# stm32103c8t6-10x10-v1.net
KiCad netlist of a schematic drawn in EAGLE
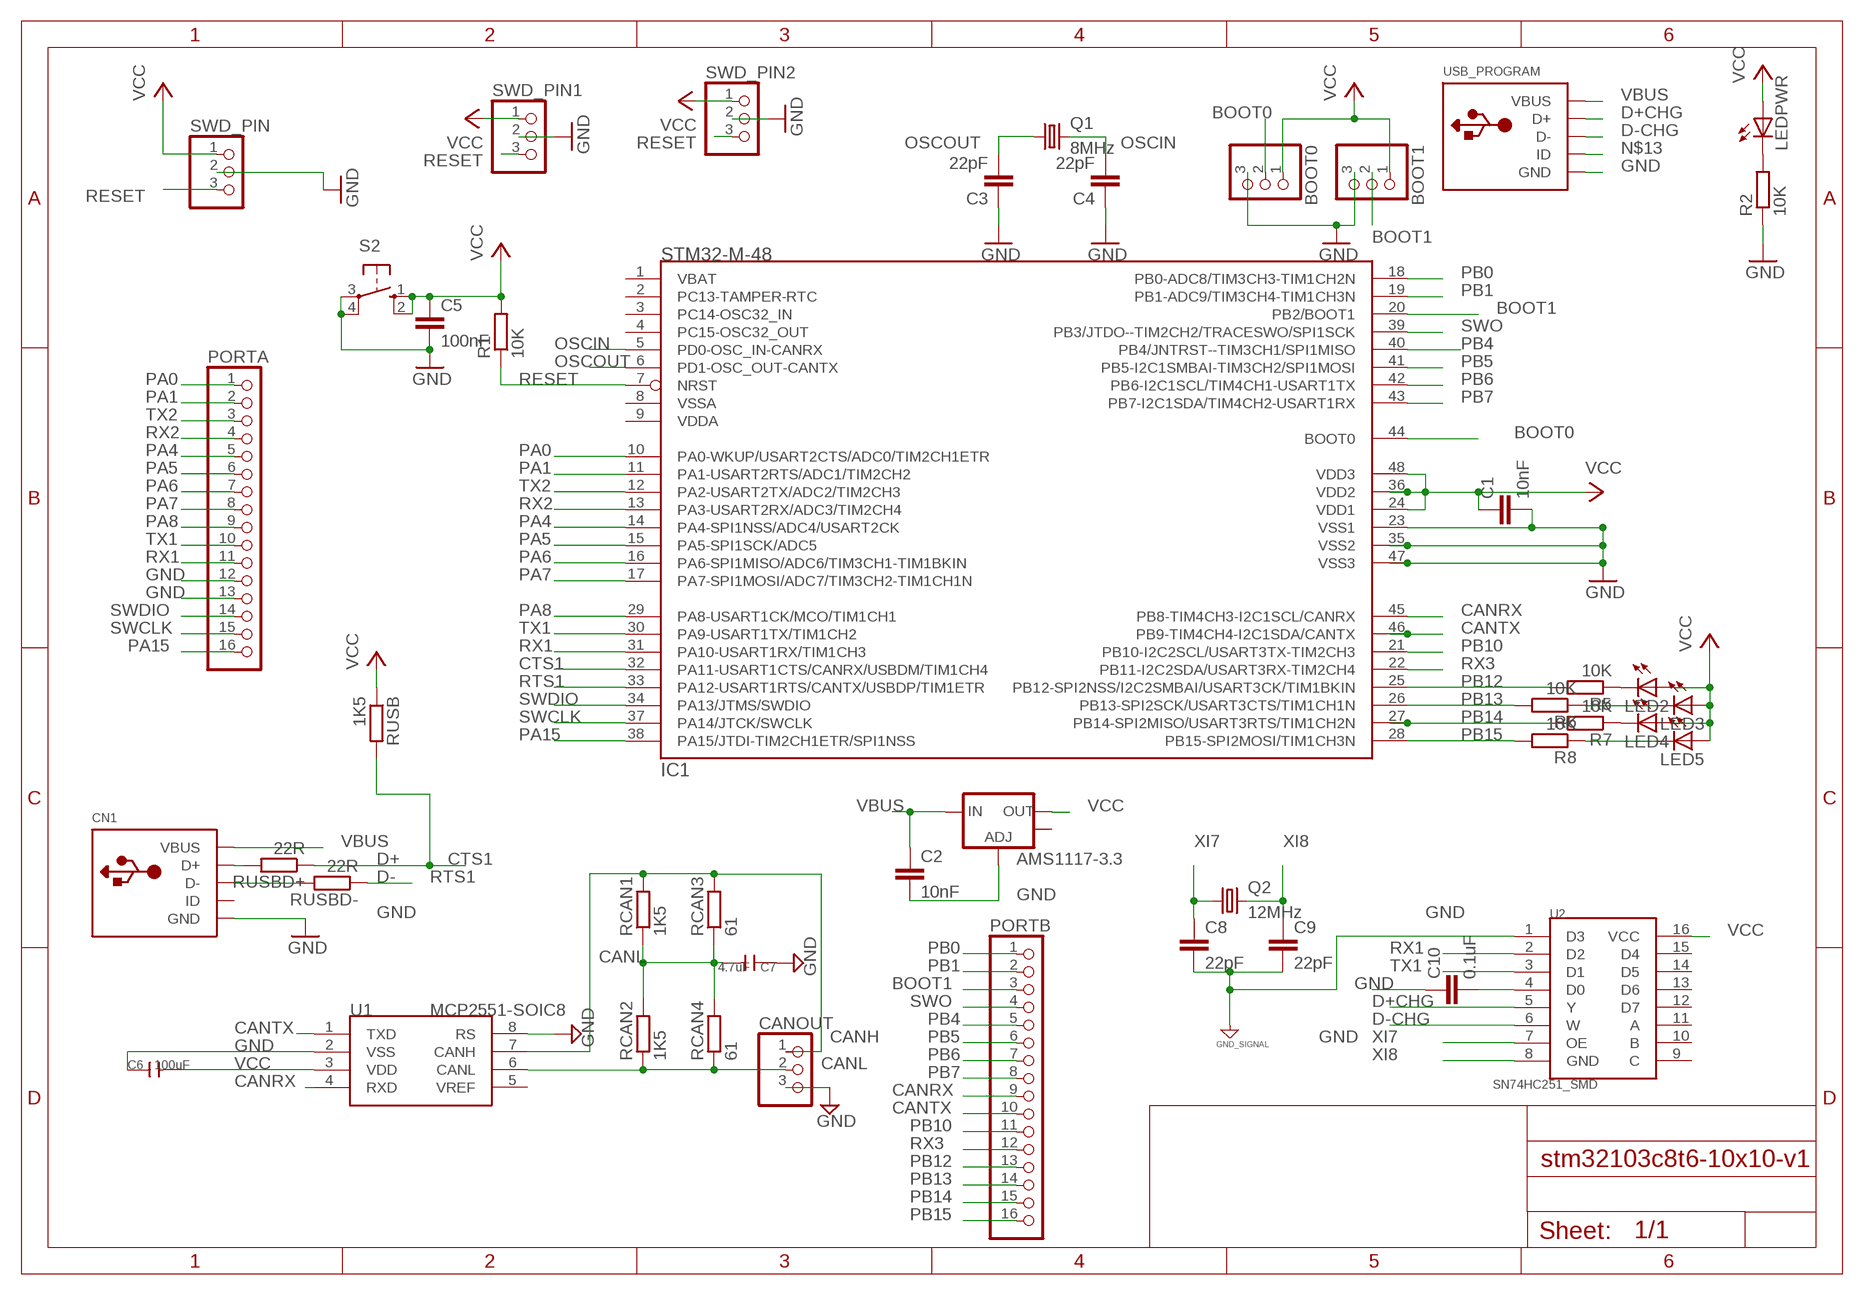
[diagram p0: schematic, sheet 1]

(export (version "E")
  (design (tool "Eeschema 10.0.6"))
  (components
    (comp (ref "AMS1117-3.3")
      (value "V_REG_LM1117SOT223")
      (footprint "eagle-import:SOT223")
      (libsource (lib "eagle-import") (part "V_REG_LM1117SOT223"))
    )
    (comp (ref "BOOT0")
      (value "PINHD-1X3")
      (footprint "eagle-import:1X03")
      (libsource (lib "eagle-import") (part "PINHD-1X3"))
    )
    (comp (ref "BOOT1")
      (value "PINHD-1X3")
      (footprint "eagle-import:1X03")
      (libsource (lib "eagle-import") (part "PINHD-1X3"))
    )
    (comp (ref "C1")
      (value "10nF")
      (footprint "eagle-import:C1210")
      (libsource (lib "eagle-import") (part "C-EUC1210"))
    )
    (comp (ref "C2")
      (value "10nF")
      (footprint "eagle-import:C1206")
      (libsource (lib "eagle-import") (part "C-EUC1206"))
    )
    (comp (ref "C3")
      (value "22pF")
      (footprint "eagle-import:C1210")
      (libsource (lib "eagle-import") (part "C-EUC1210"))
    )
    (comp (ref "C4")
      (value "22pF")
      (footprint "eagle-import:C1210")
      (libsource (lib "eagle-import") (part "C-EUC1210"))
    )
    (comp (ref "C5")
      (value "100nF")
      (footprint "eagle-import:C1206")
      (libsource (lib "eagle-import") (part "C-EUC1206"))
    )
    (comp (ref "C6")
      (value "100uF")
      (footprint "eagle-import:C1206")
      (libsource (lib "eagle-import") (part "C-1206"))
    )
    (comp (ref "C7")
      (value "4.7uF")
      (footprint "eagle-import:C1206")
      (libsource (lib "eagle-import") (part "C-1206"))
    )
    (comp (ref "C8")
      (value "22pF")
      (footprint "eagle-import:C1206")
      (libsource (lib "eagle-import") (part "C-EUC1206"))
    )
    (comp (ref "C9")
      (value "22pF")
      (footprint "eagle-import:C1206")
      (libsource (lib "eagle-import") (part "C-EUC1206"))
    )
    (comp (ref "C10")
      (value "0.1uF")
      (footprint "eagle-import:C1206")
      (libsource (lib "eagle-import") (part "C-EUC1206"))
    )
    (comp (ref "CANOUT")
      (value "PINHD-1X3")
      (footprint "eagle-import:1X03")
      (libsource (lib "eagle-import") (part "PINHD-1X3"))
    )
    (comp (ref "CN1")
      (value "USBTHM")
      (footprint "eagle-import:USB-MINIB-THM")
      (libsource (lib "eagle-import") (part "USBTHM"))
    )
    (comp (ref "IC1")
      (value "STM32-M-48")
      (footprint "eagle-import:LQFP48")
      (libsource (lib "eagle-import") (part "STM32-M-48"))
    )
    (comp (ref "LED2")
      (value "LEDSMT1206")
      (footprint "eagle-import:1206")
      (libsource (lib "eagle-import") (part "LEDSMT1206"))
    )
    (comp (ref "LED3")
      (value "LEDSMT1206")
      (footprint "eagle-import:1206")
      (libsource (lib "eagle-import") (part "LEDSMT1206"))
    )
    (comp (ref "LED4")
      (value "LEDSMT1206")
      (footprint "eagle-import:1206")
      (libsource (lib "eagle-import") (part "LEDSMT1206"))
    )
    (comp (ref "LED5")
      (value "LEDSMT1206")
      (footprint "eagle-import:1206")
      (libsource (lib "eagle-import") (part "LEDSMT1206"))
    )
    (comp (ref "LEDPWR")
      (value "LEDSMT1206")
      (footprint "eagle-import:1206")
      (libsource (lib "eagle-import") (part "LEDSMT1206"))
    )
    (comp (ref "PORTA")
      (value "PINHD-1X16")
      (footprint "eagle-import:1X16")
      (libsource (lib "eagle-import") (part "PINHD-1X16"))
    )
    (comp (ref "PORTB")
      (value "PINHD-1X16")
      (footprint "eagle-import:1X16")
      (libsource (lib "eagle-import") (part "PINHD-1X16"))
    )
    (comp (ref "Q1")
      (value "8MHz")
      (footprint "eagle-import:HC49_S")
      (libsource (lib "eagle-import") (part "CRYSTALHC49S"))
    )
    (comp (ref "Q2")
      (value "12MHz")
      (footprint "eagle-import:HC49_S")
      (libsource (lib "eagle-import") (part "CRYSTALHC49S"))
    )
    (comp (ref "R1")
      (value "10K")
      (footprint "eagle-import:R1206")
      (libsource (lib "eagle-import") (part "R-EU_R1206"))
    )
    (comp (ref "R2")
      (value "10K")
      (footprint "eagle-import:R1206")
      (libsource (lib "eagle-import") (part "R-EU_R1206"))
    )
    (comp (ref "R5")
      (value "10K")
      (footprint "eagle-import:R1206")
      (libsource (lib "eagle-import") (part "R-EU_R1206"))
    )
    (comp (ref "R6")
      (value "10K")
      (footprint "eagle-import:R1206")
      (libsource (lib "eagle-import") (part "R-EU_R1206"))
    )
    (comp (ref "R7")
      (value "10K")
      (footprint "eagle-import:R1206")
      (libsource (lib "eagle-import") (part "R-EU_R1206"))
    )
    (comp (ref "R8")
      (value "10K")
      (footprint "eagle-import:R1206")
      (libsource (lib "eagle-import") (part "R-EU_R1206"))
    )
    (comp (ref "RCAN1")
      (value "1K5")
      (footprint "eagle-import:R1206")
      (libsource (lib "eagle-import") (part "R-EU_R1206"))
    )
    (comp (ref "RCAN2")
      (value "1K5")
      (footprint "eagle-import:R1206")
      (libsource (lib "eagle-import") (part "R-EU_R1206"))
    )
    (comp (ref "RCAN3")
      (value "61")
      (footprint "eagle-import:R1206")
      (libsource (lib "eagle-import") (part "R-EU_R1206"))
    )
    (comp (ref "RCAN4")
      (value "61")
      (footprint "eagle-import:R1206")
      (libsource (lib "eagle-import") (part "R-EU_R1206"))
    )
    (comp (ref "RUSB")
      (value "1K5")
      (footprint "eagle-import:R1206")
      (libsource (lib "eagle-import") (part "R-EU_R1206"))
    )
    (comp (ref "RUSBD+")
      (value "22R")
      (footprint "eagle-import:R1206")
      (libsource (lib "eagle-import") (part "R-EU_R1206"))
    )
    (comp (ref "RUSBD-")
      (value "22R")
      (footprint "eagle-import:R1206")
      (libsource (lib "eagle-import") (part "R-EU_R1206"))
    )
    (comp (ref "S2")
      (value "10-XX")
      (footprint "eagle-import:B3F-10XX")
      (fields (field (name "MPN") "B3F-1000"))
      (libsource (lib "eagle-import") (part "10-XX"))
    )
    (comp (ref "SWD_PIN")
      (value "PINHD-1X3")
      (footprint "eagle-import:1X03")
      (libsource (lib "eagle-import") (part "PINHD-1X3"))
    )
    (comp (ref "SWD_PIN1")
      (value "PINHD-1X3")
      (footprint "eagle-import:1X03")
      (libsource (lib "eagle-import") (part "PINHD-1X3"))
    )
    (comp (ref "SWD_PIN2")
      (value "PINHD-1X3")
      (footprint "eagle-import:1X03")
      (libsource (lib "eagle-import") (part "PINHD-1X3"))
    )
    (comp (ref "U1")
      (value "MCP2551-SOIC8")
      (footprint "eagle-import:SOIC8-6.0")
      (libsource (lib "eagle-import") (part "MCP2551-SOIC8"))
    )
    (comp (ref "U2")
      (value "SN74HC251_SMD")
      (footprint "eagle-import:SO016")
      (libsource (lib "eagle-import") (part "SN74HC251_SMD"))
    )
    (comp (ref "USB_PROGRAM")
      (value "USBTHM")
      (footprint "eagle-import:USB-MINIB-THM")
      (libsource (lib "eagle-import") (part "USBTHM"))
    )
  )
  (nets
    (net (code "1") (name "/BOOT0") (class "Default")
      (node (ref "BOOT0") (pin "2") (pinfunction "2_2") (pintype "passive"))
      (node (ref "IC1") (pin "44") (pinfunction "BOOT0_44") (pintype "input"))
    )
    (net (code "2") (name "/BOOT1") (class "Default")
      (node (ref "BOOT1") (pin "2") (pinfunction "2_2") (pintype "passive"))
      (node (ref "IC1") (pin "20") (pinfunction "PB2/BOOT1_20") (pintype "bidirectional"))
      (node (ref "PORTB") (pin "3") (pinfunction "3_3") (pintype "passive"))
    )
    (net (code "3") (name "/CANH") (class "Default")
      (node (ref "CANOUT") (pin "1") (pinfunction "1_1") (pintype "passive"))
      (node (ref "RCAN1") (pin "2") (pinfunction "2_2") (pintype "passive"))
      (node (ref "RCAN3") (pin "2") (pinfunction "2_2") (pintype "passive"))
      (node (ref "U1") (pin "7") (pinfunction "CANH_7") (pintype "bidirectional"))
    )
    (net (code "4") (name "/CANL") (class "Default")
      (node (ref "CANOUT") (pin "2") (pinfunction "2_2") (pintype "passive"))
      (node (ref "RCAN2") (pin "1") (pinfunction "1_1") (pintype "passive"))
      (node (ref "RCAN4") (pin "1") (pinfunction "1_1") (pintype "passive"))
      (node (ref "U1") (pin "6") (pinfunction "CANL_6") (pintype "bidirectional"))
    )
    (net (code "5") (name "/CANRX") (class "Default")
      (node (ref "IC1") (pin "45") (pinfunction "PB8-TIM4CH3-I2C1SCL/CANRX_45") (pintype "bidirectional"))
      (node (ref "PORTB") (pin "9") (pinfunction "9_9") (pintype "passive"))
      (node (ref "U1") (pin "4") (pinfunction "RXD_4") (pintype "bidirectional"))
    )
    (net (code "6") (name "/CANTX") (class "Default")
      (node (ref "IC1") (pin "46") (pinfunction "PB9-TIM4CH4-I2C1SDA/CANTX_46") (pintype "bidirectional"))
      (node (ref "PORTB") (pin "10") (pinfunction "10_10") (pintype "passive"))
      (node (ref "U1") (pin "1") (pinfunction "TXD_1") (pintype "bidirectional"))
    )
    (net (code "7") (name "/CTS1") (class "Default")
      (node (ref "IC1") (pin "32") (pinfunction "PA11-USART1CTS/CANRX/USBDM/TIM1CH4_32") (pintype "bidirectional"))
      (node (ref "RUSB") (pin "2") (pinfunction "2_2") (pintype "passive"))
      (node (ref "RUSBD+") (pin "1") (pinfunction "1_1") (pintype "passive"))
    )
    (net (code "8") (name "/D+") (class "Default")
      (node (ref "CN1") (pin "D+") (pinfunction "D+_D+") (pintype "bidirectional"))
      (node (ref "RUSBD+") (pin "2") (pinfunction "2_2") (pintype "passive"))
    )
    (net (code "9") (name "/D+CHG") (class "Default")
      (node (ref "U2") (pin "5") (pinfunction "Y_5") (pintype "bidirectional"))
      (node (ref "USB_PROGRAM") (pin "D+") (pinfunction "D+_D+") (pintype "bidirectional"))
    )
    (net (code "10") (name "/D-") (class "Default")
      (node (ref "CN1") (pin "D-") (pinfunction "D-_D-") (pintype "bidirectional"))
      (node (ref "RUSBD-") (pin "2") (pinfunction "2_2") (pintype "passive"))
    )
    (net (code "11") (name "/D-CHG") (class "Default")
      (node (ref "U2") (pin "6") (pinfunction "W_6") (pintype "bidirectional"))
      (node (ref "USB_PROGRAM") (pin "D-") (pinfunction "D-_D-") (pintype "bidirectional"))
    )
    (net (code "12") (name "/N$13") (class "Default")
      (node (ref "USB_PROGRAM") (pin "ID") (pinfunction "ID_ID") (pintype "bidirectional"))
    )
    (net (code "13") (name "/OSCIN") (class "Default")
      (node (ref "C4") (pin "2") (pinfunction "2_2") (pintype "passive"))
      (node (ref "IC1") (pin "5") (pinfunction "PD0-OSC_IN-CANRX_5") (pintype "input"))
      (node (ref "Q1") (pin "2") (pinfunction "2_2") (pintype "passive"))
    )
    (net (code "14") (name "/OSCOUT") (class "Default")
      (node (ref "C3") (pin "2") (pinfunction "2_2") (pintype "passive"))
      (node (ref "IC1") (pin "6") (pinfunction "PD1-OSC_OUT-CANTX_6") (pintype "output"))
      (node (ref "Q1") (pin "1") (pinfunction "1_1") (pintype "passive"))
    )
    (net (code "15") (name "/PA0") (class "Default")
      (node (ref "IC1") (pin "10") (pinfunction "PA0-WKUP/USART2CTS/ADC0/TIM2CH1ETR_10") (pintype "bidirectional"))
      (node (ref "PORTA") (pin "1") (pinfunction "1_1") (pintype "passive"))
    )
    (net (code "16") (name "/PA1") (class "Default")
      (node (ref "IC1") (pin "11") (pinfunction "PA1-USART2RTS/ADC1/TIM2CH2_11") (pintype "bidirectional"))
      (node (ref "PORTA") (pin "2") (pinfunction "2_2") (pintype "passive"))
    )
    (net (code "17") (name "/PA4") (class "Default")
      (node (ref "IC1") (pin "14") (pinfunction "PA4-SPI1NSS/ADC4/USART2CK_14") (pintype "bidirectional"))
      (node (ref "PORTA") (pin "5") (pinfunction "5_5") (pintype "passive"))
    )
    (net (code "18") (name "/PA5") (class "Default")
      (node (ref "IC1") (pin "15") (pinfunction "PA5-SPI1SCK/ADC5_15") (pintype "bidirectional"))
      (node (ref "PORTA") (pin "6") (pinfunction "6_6") (pintype "passive"))
    )
    (net (code "19") (name "/PA6") (class "Default")
      (node (ref "IC1") (pin "16") (pinfunction "PA6-SPI1MISO/ADC6/TIM3CH1-TIM1BKIN_16") (pintype "bidirectional"))
      (node (ref "PORTA") (pin "7") (pinfunction "7_7") (pintype "passive"))
    )
    (net (code "20") (name "/PA7") (class "Default")
      (node (ref "IC1") (pin "17") (pinfunction "PA7-SPI1MOSI/ADC7/TIM3CH2-TIM1CH1N_17") (pintype "bidirectional"))
      (node (ref "PORTA") (pin "8") (pinfunction "8_8") (pintype "passive"))
    )
    (net (code "21") (name "/PA8") (class "Default")
      (node (ref "IC1") (pin "29") (pinfunction "PA8-USART1CK/MCO/TIM1CH1_29") (pintype "bidirectional"))
      (node (ref "PORTA") (pin "9") (pinfunction "9_9") (pintype "passive"))
    )
    (net (code "22") (name "/PA15") (class "Default")
      (node (ref "IC1") (pin "38") (pinfunction "PA15/JTDI-TIM2CH1ETR/SPI1NSS_38") (pintype "bidirectional"))
      (node (ref "PORTA") (pin "16") (pinfunction "16_16") (pintype "passive"))
    )
    (net (code "23") (name "/PB0") (class "Default")
      (node (ref "IC1") (pin "18") (pinfunction "PB0-ADC8/TIM3CH3-TIM1CH2N_18") (pintype "bidirectional"))
      (node (ref "PORTB") (pin "1") (pinfunction "1_1") (pintype "passive"))
    )
    (net (code "24") (name "/PB1") (class "Default")
      (node (ref "IC1") (pin "19") (pinfunction "PB1-ADC9/TIM3CH4-TIM1CH3N_19") (pintype "bidirectional"))
      (node (ref "PORTB") (pin "2") (pinfunction "2_2") (pintype "passive"))
    )
    (net (code "25") (name "/PB4") (class "Default")
      (node (ref "IC1") (pin "40") (pinfunction "PB4/JNTRST--TIM3CH1/SPI1MISO_40") (pintype "bidirectional"))
      (node (ref "PORTB") (pin "5") (pinfunction "5_5") (pintype "passive"))
    )
    (net (code "26") (name "/PB5") (class "Default")
      (node (ref "IC1") (pin "41") (pinfunction "PB5-I2C1SMBAI-TIM3CH2/SPI1MOSI_41") (pintype "bidirectional"))
      (node (ref "PORTB") (pin "6") (pinfunction "6_6") (pintype "passive"))
    )
    (net (code "27") (name "/PB6") (class "Default")
      (node (ref "IC1") (pin "42") (pinfunction "PB6-I2C1SCL/TIM4CH1-USART1TX_42") (pintype "bidirectional"))
      (node (ref "PORTB") (pin "7") (pinfunction "7_7") (pintype "passive"))
    )
    (net (code "28") (name "/PB7") (class "Default")
      (node (ref "IC1") (pin "43") (pinfunction "PB7-I2C1SDA/TIM4CH2-USART1RX_43") (pintype "bidirectional"))
      (node (ref "PORTB") (pin "8") (pinfunction "8_8") (pintype "passive"))
    )
    (net (code "29") (name "/PB10") (class "Default")
      (node (ref "IC1") (pin "21") (pinfunction "PB10-I2C2SCL/USART3TX-TIM2CH3_21") (pintype "bidirectional"))
      (node (ref "PORTB") (pin "11") (pinfunction "11_11") (pintype "passive"))
    )
    (net (code "30") (name "/PB12") (class "Default")
      (node (ref "IC1") (pin "25") (pinfunction "PB12-SPI2NSS/I2C2SMBAI/USART3CK/TIM1BKIN_25") (pintype "bidirectional"))
      (node (ref "PORTB") (pin "13") (pinfunction "13_13") (pintype "passive"))
      (node (ref "R5") (pin "2") (pinfunction "2_2") (pintype "passive"))
    )
    (net (code "31") (name "/PB13") (class "Default")
      (node (ref "IC1") (pin "26") (pinfunction "PB13-SPI2SCK/USART3CTS/TIM1CH1N_26") (pintype "bidirectional"))
      (node (ref "PORTB") (pin "14") (pinfunction "14_14") (pintype "passive"))
      (node (ref "R6") (pin "2") (pinfunction "2_2") (pintype "passive"))
    )
    (net (code "32") (name "/PB14") (class "Default")
      (node (ref "IC1") (pin "27") (pinfunction "PB14-SPI2MISO/USART3RTS/TIM1CH2N_27") (pintype "bidirectional"))
      (node (ref "PORTB") (pin "15") (pinfunction "15_15") (pintype "passive"))
      (node (ref "R7") (pin "2") (pinfunction "2_2") (pintype "passive"))
    )
    (net (code "33") (name "/PB15") (class "Default")
      (node (ref "IC1") (pin "28") (pinfunction "PB15-SPI2MOSI/TIM1CH3N_28") (pintype "bidirectional"))
      (node (ref "PORTB") (pin "16") (pinfunction "16_16") (pintype "passive"))
      (node (ref "R8") (pin "2") (pinfunction "2_2") (pintype "passive"))
    )
    (net (code "34") (name "/RESET") (class "Default")
      (node (ref "IC1") (pin "7") (pinfunction "NRST_7") (pintype "bidirectional"))
      (node (ref "R1") (pin "1") (pinfunction "1_1") (pintype "passive"))
      (node (ref "SWD_PIN") (pin "3") (pinfunction "3_3") (pintype "passive"))
      (node (ref "SWD_PIN1") (pin "3") (pinfunction "3_3") (pintype "passive"))
      (node (ref "SWD_PIN2") (pin "3") (pinfunction "3_3") (pintype "passive"))
    )
    (net (code "35") (name "/RTS1") (class "Default")
      (node (ref "IC1") (pin "33") (pinfunction "PA12-USART1RTS/CANTX/USBDP/TIM1ETR_33") (pintype "bidirectional"))
      (node (ref "RUSBD-") (pin "1") (pinfunction "1_1") (pintype "passive"))
    )
    (net (code "36") (name "/RX1") (class "Default")
      (node (ref "IC1") (pin "31") (pinfunction "PA10-USART1RX/TIM1CH3_31") (pintype "bidirectional"))
      (node (ref "PORTA") (pin "11") (pinfunction "11_11") (pintype "passive"))
      (node (ref "U2") (pin "2") (pinfunction "D2_2") (pintype "bidirectional"))
    )
    (net (code "37") (name "/RX2") (class "Default")
      (node (ref "IC1") (pin "13") (pinfunction "PA3-USART2RX/ADC3/TIM2CH4_13") (pintype "bidirectional"))
      (node (ref "PORTA") (pin "4") (pinfunction "4_4") (pintype "passive"))
    )
    (net (code "38") (name "/RX3") (class "Default")
      (node (ref "IC1") (pin "22") (pinfunction "PB11-I2C2SDA/USART3RX-TIM2CH4_22") (pintype "bidirectional"))
      (node (ref "PORTB") (pin "12") (pinfunction "12_12") (pintype "passive"))
    )
    (net (code "39") (name "/SWCLK") (class "Default")
      (node (ref "IC1") (pin "37") (pinfunction "PA14/JTCK/SWCLK_37") (pintype "bidirectional"))
      (node (ref "PORTA") (pin "15") (pinfunction "15_15") (pintype "passive"))
    )
    (net (code "40") (name "/SWDIO") (class "Default")
      (node (ref "IC1") (pin "34") (pinfunction "PA13/JTMS/SWDIO_34") (pintype "bidirectional"))
      (node (ref "PORTA") (pin "14") (pinfunction "14_14") (pintype "passive"))
    )
    (net (code "41") (name "/SWO") (class "Default")
      (node (ref "IC1") (pin "39") (pinfunction "PB3/JTDO--TIM2CH2/TRACESWO/SPI1SCK_39") (pintype "bidirectional"))
      (node (ref "PORTB") (pin "4") (pinfunction "4_4") (pintype "passive"))
    )
    (net (code "42") (name "/TX1") (class "Default")
      (node (ref "IC1") (pin "30") (pinfunction "PA9-USART1TX/TIM1CH2_30") (pintype "bidirectional"))
      (node (ref "PORTA") (pin "10") (pinfunction "10_10") (pintype "passive"))
      (node (ref "U2") (pin "3") (pinfunction "D1_3") (pintype "bidirectional"))
    )
    (net (code "43") (name "/TX2") (class "Default")
      (node (ref "IC1") (pin "12") (pinfunction "PA2-USART2TX/ADC2/TIM2CH3_12") (pintype "bidirectional"))
      (node (ref "PORTA") (pin "3") (pinfunction "3_3") (pintype "passive"))
    )
    (net (code "44") (name "/VBAT") (class "Default")
      (node (ref "IC1") (pin "1") (pinfunction "VBAT_1") (pintype "power_in"))
    )
    (net (code "45") (name "/VBUS") (class "Default")
      (node (ref "AMS1117-3.3") (pin "3") (pinfunction "IN_3") (pintype "input"))
      (node (ref "C2") (pin "1") (pinfunction "1_1") (pintype "passive"))
      (node (ref "CN1") (pin "VBUS") (pinfunction "VBUS_VBUS") (pintype "power_in"))
      (node (ref "USB_PROGRAM") (pin "VBUS") (pinfunction "VBUS_VBUS") (pintype "power_in"))
    )
    (net (code "46") (name "/VDDA") (class "Default")
      (node (ref "IC1") (pin "9") (pinfunction "VDDA_9") (pintype "power_in"))
    )
    (net (code "47") (name "/VSSA") (class "Default")
      (node (ref "IC1") (pin "8") (pinfunction "VSSA_8") (pintype "power_in"))
    )
    (net (code "48") (name "/XI7") (class "Default")
      (node (ref "C8") (pin "1") (pinfunction "1_1") (pintype "passive"))
      (node (ref "Q2") (pin "1") (pinfunction "1_1") (pintype "passive"))
      (node (ref "U2") (pin "7") (pinfunction "OE_7") (pintype "bidirectional"))
    )
    (net (code "49") (name "/XI8") (class "Default")
      (node (ref "C9") (pin "1") (pinfunction "1_1") (pintype "passive"))
      (node (ref "Q2") (pin "2") (pinfunction "2_2") (pintype "passive"))
      (node (ref "U2") (pin "8") (pinfunction "GND_8") (pintype "bidirectional"))
    )
    (net (code "50") (name "GND") (class "Default")
      (node (ref "AMS1117-3.3") (pin "1") (pinfunction "ADJ_1") (pintype "input"))
      (node (ref "BOOT0") (pin "3") (pinfunction "3_3") (pintype "passive"))
      (node (ref "BOOT1") (pin "3") (pinfunction "3_3") (pintype "passive"))
      (node (ref "C1") (pin "2") (pinfunction "2_2") (pintype "passive"))
      (node (ref "C10") (pin "1") (pinfunction "1_1") (pintype "passive"))
      (node (ref "C2") (pin "2") (pinfunction "2_2") (pintype "passive"))
      (node (ref "C3") (pin "1") (pinfunction "1_1") (pintype "passive"))
      (node (ref "C4") (pin "1") (pinfunction "1_1") (pintype "passive"))
      (node (ref "C5") (pin "2") (pinfunction "2_2") (pintype "passive"))
      (node (ref "C6") (pin "1") (pinfunction "1_1") (pintype "passive"))
      (node (ref "C7") (pin "1") (pinfunction "1_1") (pintype "passive"))
      (node (ref "C8") (pin "2") (pinfunction "2_2") (pintype "passive"))
      (node (ref "C9") (pin "2") (pinfunction "2_2") (pintype "passive"))
      (node (ref "CANOUT") (pin "3") (pinfunction "3_3") (pintype "passive"))
      (node (ref "CN1") (pin "GND") (pinfunction "GND_GND") (pintype "power_in"))
      (node (ref "IC1") (pin "23") (pinfunction "VSS1_23") (pintype "power_in"))
      (node (ref "IC1") (pin "35") (pinfunction "VSS2_35") (pintype "power_in"))
      (node (ref "IC1") (pin "47") (pinfunction "VSS3_47") (pintype "power_in"))
      (node (ref "PORTA") (pin "12") (pinfunction "12_12") (pintype "passive"))
      (node (ref "PORTA") (pin "13") (pinfunction "13_13") (pintype "passive"))
      (node (ref "R2") (pin "1") (pinfunction "1_1") (pintype "passive"))
      (node (ref "S2") (pin "3") (pinfunction "P_3") (pintype "passive"))
      (node (ref "S2") (pin "4") (pinfunction "P1_4") (pintype "passive"))
      (node (ref "SWD_PIN") (pin "2") (pinfunction "2_2") (pintype "passive"))
      (node (ref "SWD_PIN1") (pin "2") (pinfunction "2_2") (pintype "passive"))
      (node (ref "SWD_PIN2") (pin "2") (pinfunction "2_2") (pintype "passive"))
      (node (ref "U1") (pin "2") (pinfunction "VSS_2") (pintype "bidirectional"))
      (node (ref "U1") (pin "8") (pinfunction "RS_8") (pintype "bidirectional"))
      (node (ref "U2") (pin "1") (pinfunction "D3_1") (pintype "bidirectional"))
      (node (ref "USB_PROGRAM") (pin "GND") (pinfunction "GND_GND") (pintype "power_in"))
    )
    (net (code "51") (name "Net-(C7-Pad2)") (class "Default")
      (node (ref "C7") (pin "2") (pinfunction "2_2") (pintype "passive"))
      (node (ref "RCAN1") (pin "1") (pinfunction "1_1") (pintype "passive"))
      (node (ref "RCAN2") (pin "2") (pinfunction "2_2") (pintype "passive"))
      (node (ref "RCAN3") (pin "1") (pinfunction "1_1") (pintype "passive"))
      (node (ref "RCAN4") (pin "2") (pinfunction "2_2") (pintype "passive"))
    )
    (net (code "52") (name "Net-(LED2-PadC)") (class "Default")
      (node (ref "LED2") (pin "C") (pinfunction "C_C") (pintype "passive"))
      (node (ref "R5") (pin "1") (pinfunction "1_1") (pintype "passive"))
    )
    (net (code "53") (name "Net-(LED3-PadC)") (class "Default")
      (node (ref "LED3") (pin "C") (pinfunction "C_C") (pintype "passive"))
      (node (ref "R6") (pin "1") (pinfunction "1_1") (pintype "passive"))
    )
    (net (code "54") (name "Net-(LED4-PadC)") (class "Default")
      (node (ref "LED4") (pin "C") (pinfunction "C_C") (pintype "passive"))
      (node (ref "R7") (pin "1") (pinfunction "1_1") (pintype "passive"))
    )
    (net (code "55") (name "Net-(LED5-PadC)") (class "Default")
      (node (ref "LED5") (pin "C") (pinfunction "C_C") (pintype "passive"))
      (node (ref "R8") (pin "1") (pinfunction "1_1") (pintype "passive"))
    )
    (net (code "56") (name "Net-(LEDPWR-PadC)") (class "Default")
      (node (ref "LEDPWR") (pin "C") (pinfunction "C_C") (pintype "passive"))
      (node (ref "R2") (pin "2") (pinfunction "2_2") (pintype "passive"))
    )
    (net (code "57") (name "Net-(U2-D0)") (class "Default")
      (node (ref "C10") (pin "2") (pinfunction "2_2") (pintype "passive"))
      (node (ref "U2") (pin "4") (pinfunction "D0_4") (pintype "bidirectional"))
    )
    (net (code "58") (name "VCC") (class "Default")
      (node (ref "AMS1117-3.3") (pin "2") (pinfunction "OUT_2") (pintype "output"))
      (node (ref "BOOT0") (pin "1") (pinfunction "1_1") (pintype "passive"))
      (node (ref "BOOT1") (pin "1") (pinfunction "1_1") (pintype "passive"))
      (node (ref "C1") (pin "1") (pinfunction "1_1") (pintype "passive"))
      (node (ref "C5") (pin "1") (pinfunction "1_1") (pintype "passive"))
      (node (ref "C6") (pin "2") (pinfunction "2_2") (pintype "passive"))
      (node (ref "IC1") (pin "24") (pinfunction "VDD1_24") (pintype "power_in"))
      (node (ref "IC1") (pin "36") (pinfunction "VDD2_36") (pintype "power_in"))
      (node (ref "IC1") (pin "48") (pinfunction "VDD3_48") (pintype "power_in"))
      (node (ref "LED2") (pin "A") (pinfunction "A_A") (pintype "passive"))
      (node (ref "LED3") (pin "A") (pinfunction "A_A") (pintype "passive"))
      (node (ref "LED4") (pin "A") (pinfunction "A_A") (pintype "passive"))
      (node (ref "LED5") (pin "A") (pinfunction "A_A") (pintype "passive"))
      (node (ref "LEDPWR") (pin "A") (pinfunction "A_A") (pintype "passive"))
      (node (ref "R1") (pin "2") (pinfunction "2_2") (pintype "passive"))
      (node (ref "RUSB") (pin "1") (pinfunction "1_1") (pintype "passive"))
      (node (ref "S2") (pin "1") (pinfunction "S_1") (pintype "passive"))
      (node (ref "S2") (pin "2") (pinfunction "S1_2") (pintype "passive"))
      (node (ref "SWD_PIN") (pin "1") (pinfunction "1_1") (pintype "passive"))
      (node (ref "SWD_PIN1") (pin "1") (pinfunction "1_1") (pintype "passive"))
      (node (ref "SWD_PIN2") (pin "1") (pinfunction "1_1") (pintype "passive"))
      (node (ref "U1") (pin "3") (pinfunction "VDD_3") (pintype "bidirectional"))
      (node (ref "U2") (pin "16") (pinfunction "VCC_16") (pintype "bidirectional"))
    )
    (net (code "59") (name "unconnected-(AMS1117-3.3-OUT-Pad4)") (class "Default")
      (node (ref "AMS1117-3.3") (pin "4") (pinfunction "OUT_4") (pintype "output"))
    )
    (net (code "60") (name "unconnected-(CN1-PadID)") (class "Default")
      (node (ref "CN1") (pin "ID") (pinfunction "ID_ID") (pintype "bidirectional"))
    )
    (net (code "61") (name "unconnected-(IC1-PC13-TAMPER-RTC-Pad2)") (class "Default")
      (node (ref "IC1") (pin "2") (pinfunction "PC13-TAMPER-RTC_2") (pintype "bidirectional"))
    )
    (net (code "62") (name "unconnected-(IC1-PC14-OSC32_IN-Pad3)") (class "Default")
      (node (ref "IC1") (pin "3") (pinfunction "PC14-OSC32_IN_3") (pintype "bidirectional"))
    )
    (net (code "63") (name "unconnected-(IC1-PC15-OSC32_OUT-Pad4)") (class "Default")
      (node (ref "IC1") (pin "4") (pinfunction "PC15-OSC32_OUT_4") (pintype "bidirectional"))
    )
    (net (code "64") (name "unconnected-(U1-VREF-Pad5)") (class "Default")
      (node (ref "U1") (pin "5") (pinfunction "VREF_5") (pintype "bidirectional"))
    )
    (net (code "65") (name "unconnected-(U2-A-Pad11)") (class "Default")
      (node (ref "U2") (pin "11") (pinfunction "A_11") (pintype "bidirectional"))
    )
    (net (code "66") (name "unconnected-(U2-B-Pad10)") (class "Default")
      (node (ref "U2") (pin "10") (pinfunction "B_10") (pintype "bidirectional"))
    )
    (net (code "67") (name "unconnected-(U2-C-Pad9)") (class "Default")
      (node (ref "U2") (pin "9") (pinfunction "C_9") (pintype "bidirectional"))
    )
    (net (code "68") (name "unconnected-(U2-D4-Pad15)") (class "Default")
      (node (ref "U2") (pin "15") (pinfunction "D4_15") (pintype "bidirectional"))
    )
    (net (code "69") (name "unconnected-(U2-D5-Pad14)") (class "Default")
      (node (ref "U2") (pin "14") (pinfunction "D5_14") (pintype "bidirectional"))
    )
    (net (code "70") (name "unconnected-(U2-D6-Pad13)") (class "Default")
      (node (ref "U2") (pin "13") (pinfunction "D6_13") (pintype "bidirectional"))
    )
    (net (code "71") (name "unconnected-(U2-D7-Pad12)") (class "Default")
      (node (ref "U2") (pin "12") (pinfunction "D7_12") (pintype "bidirectional"))
    )
  )
)
